# vent_bjt2_i2c_pwm.net
KiCad netlist of a schematic drawn in EAGLE
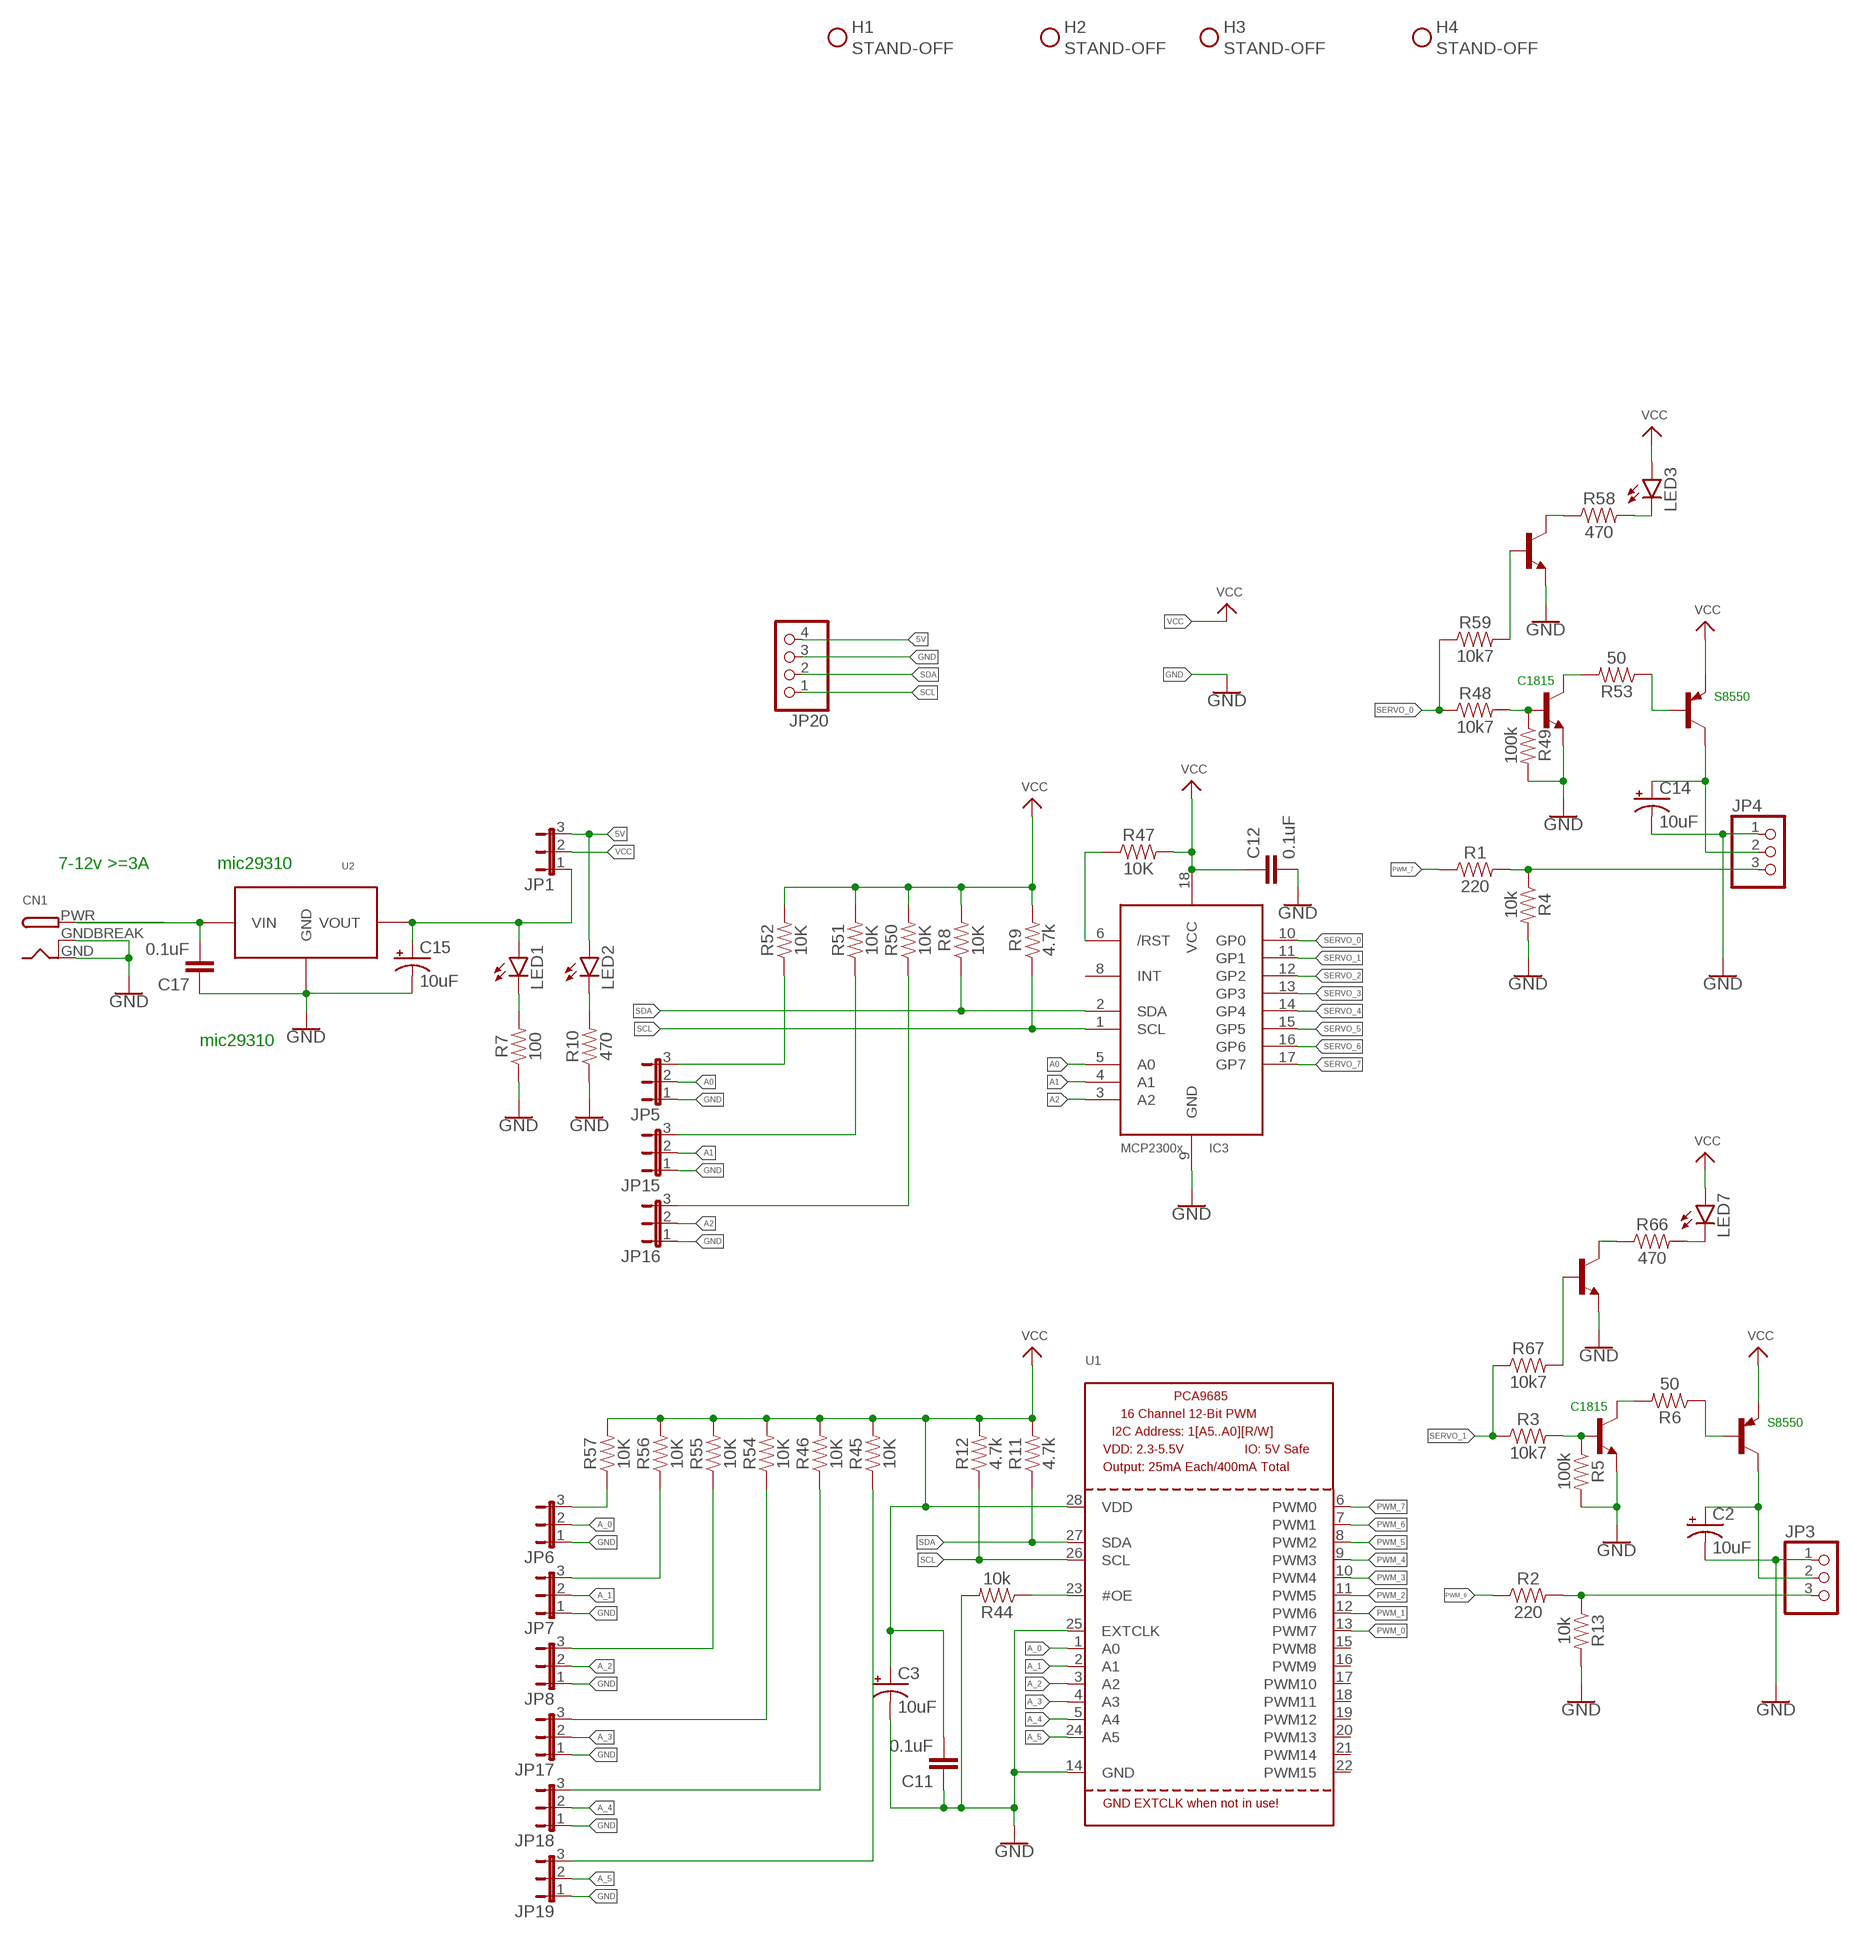
[diagram p0: schematic, sheet 1, part 1 of 2]
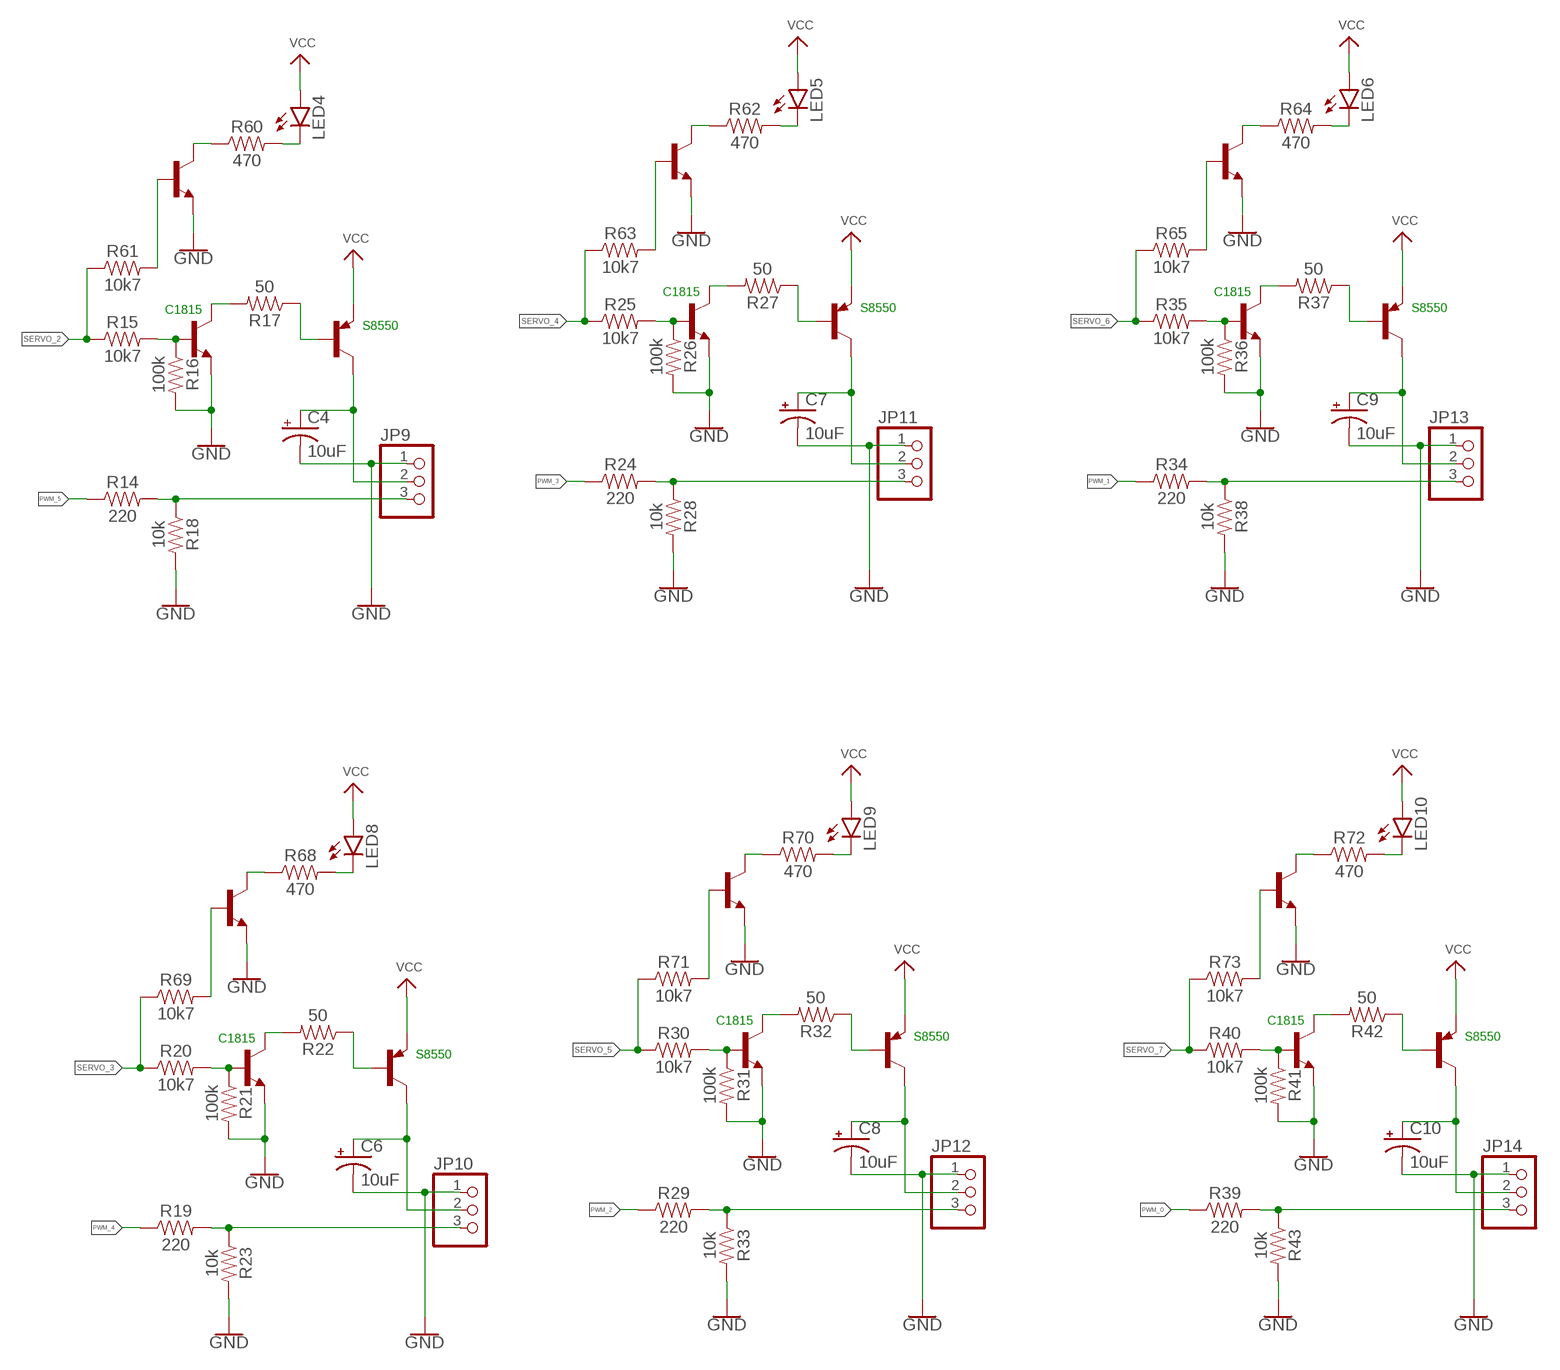
[diagram p1: schematic, sheet 1, part 2 of 2]

(export (version "E")
  (design (tool "Eeschema 10.0.6"))
  (components
    (comp (ref "C2")
      (value "10uF")
      (footprint "eagle-import:CPOL-RADIAL-2.5MM-5MM")
      (libsource (lib "eagle-import") (part "10UF-POLAR-RADIAL-2.5MM-25V-20%"))
    )
    (comp (ref "C3")
      (value "10uF")
      (footprint "eagle-import:CPOL-RADIAL-2.5MM-5MM")
      (libsource (lib "eagle-import") (part "10UF-POLAR-RADIAL-2.5MM-25V-20%"))
    )
    (comp (ref "C4")
      (value "10uF")
      (footprint "eagle-import:CPOL-RADIAL-2.5MM-5MM")
      (libsource (lib "eagle-import") (part "10UF-POLAR-RADIAL-2.5MM-25V-20%"))
    )
    (comp (ref "C6")
      (value "10uF")
      (footprint "eagle-import:CPOL-RADIAL-2.5MM-5MM")
      (libsource (lib "eagle-import") (part "10UF-POLAR-RADIAL-2.5MM-25V-20%"))
    )
    (comp (ref "C7")
      (value "10uF")
      (footprint "eagle-import:CPOL-RADIAL-2.5MM-5MM")
      (libsource (lib "eagle-import") (part "10UF-POLAR-RADIAL-2.5MM-25V-20%"))
    )
    (comp (ref "C8")
      (value "10uF")
      (footprint "eagle-import:CPOL-RADIAL-2.5MM-5MM")
      (libsource (lib "eagle-import") (part "10UF-POLAR-RADIAL-2.5MM-25V-20%"))
    )
    (comp (ref "C9")
      (value "10uF")
      (footprint "eagle-import:CPOL-RADIAL-2.5MM-5MM")
      (libsource (lib "eagle-import") (part "10UF-POLAR-RADIAL-2.5MM-25V-20%"))
    )
    (comp (ref "C10")
      (value "10uF")
      (footprint "eagle-import:CPOL-RADIAL-2.5MM-5MM")
      (libsource (lib "eagle-import") (part "10UF-POLAR-RADIAL-2.5MM-25V-20%"))
    )
    (comp (ref "C11")
      (value "0.1uF")
      (footprint "eagle-import:CAP-PTH-SMALL-KIT")
      (libsource (lib "eagle-import") (part "0.1UF-KIT-EZ-50V-20%"))
    )
    (comp (ref "C12")
      (value "0.1uF")
      (footprint "eagle-import:CAP-PTH-SMALL-KIT")
      (libsource (lib "eagle-import") (part "0.1UF-KIT-EZ-50V-20%"))
    )
    (comp (ref "C14")
      (value "10uF")
      (footprint "eagle-import:CPOL-RADIAL-2.5MM-5MM")
      (libsource (lib "eagle-import") (part "10UF-POLAR-RADIAL-2.5MM-25V-20%"))
    )
    (comp (ref "C15")
      (value "10uF")
      (footprint "eagle-import:CPOL-RADIAL-2.5MM-5MM")
      (libsource (lib "eagle-import") (part "10UF-POLAR-RADIAL-2.5MM-25V-20%"))
    )
    (comp (ref "C17")
      (value "0.1uF")
      (footprint "eagle-import:CAP-PTH-SMALL-KIT")
      (libsource (lib "eagle-import") (part "0.1UF-KIT-EZ-50V-20%"))
    )
    (comp (ref "CN1")
      (value "DCBARRELPTH")
      (footprint "eagle-import:DCJACK_2MM_PTH")
      (libsource (lib "eagle-import") (part "DCBARRELPTH"))
    )
    (comp (ref "H1")
      (value "STAND-OFF")
      (footprint "eagle-import:STAND-OFF")
      (libsource (lib "eagle-import") (part "STAND-OFF"))
    )
    (comp (ref "H2")
      (value "STAND-OFF")
      (footprint "eagle-import:STAND-OFF")
      (libsource (lib "eagle-import") (part "STAND-OFF"))
    )
    (comp (ref "H3")
      (value "STAND-OFF")
      (footprint "eagle-import:STAND-OFF")
      (libsource (lib "eagle-import") (part "STAND-OFF"))
    )
    (comp (ref "H4")
      (value "STAND-OFF")
      (footprint "eagle-import:STAND-OFF")
      (libsource (lib "eagle-import") (part "STAND-OFF"))
    )
    (comp (ref "IC3")
      (value "MCP23008/P")
      (footprint "eagle-import:DIL18")
      (libsource (lib "eagle-import") (part "MCP23008/P"))
    )
    (comp (ref "JP1")
      (value "JP2E")
      (footprint "eagle-import:JP2")
      (libsource (lib "eagle-import") (part "JP2E"))
    )
    (comp (ref "JP3")
      (value "PINHD-1X3")
      (footprint "eagle-import:1X03")
      (libsource (lib "eagle-import") (part "PINHD-1X3"))
    )
    (comp (ref "JP4")
      (value "PINHD-1X3")
      (footprint "eagle-import:1X03")
      (libsource (lib "eagle-import") (part "PINHD-1X3"))
    )
    (comp (ref "JP5")
      (value "JP2E")
      (footprint "eagle-import:JP2")
      (libsource (lib "eagle-import") (part "JP2E"))
    )
    (comp (ref "JP6")
      (value "JP2E")
      (footprint "eagle-import:JP2")
      (libsource (lib "eagle-import") (part "JP2E"))
    )
    (comp (ref "JP7")
      (value "JP2E")
      (footprint "eagle-import:JP2")
      (libsource (lib "eagle-import") (part "JP2E"))
    )
    (comp (ref "JP8")
      (value "JP2E")
      (footprint "eagle-import:JP2")
      (libsource (lib "eagle-import") (part "JP2E"))
    )
    (comp (ref "JP9")
      (value "PINHD-1X3")
      (footprint "eagle-import:1X03")
      (libsource (lib "eagle-import") (part "PINHD-1X3"))
    )
    (comp (ref "JP10")
      (value "PINHD-1X3")
      (footprint "eagle-import:1X03")
      (libsource (lib "eagle-import") (part "PINHD-1X3"))
    )
    (comp (ref "JP11")
      (value "PINHD-1X3")
      (footprint "eagle-import:1X03")
      (libsource (lib "eagle-import") (part "PINHD-1X3"))
    )
    (comp (ref "JP12")
      (value "PINHD-1X3")
      (footprint "eagle-import:1X03")
      (libsource (lib "eagle-import") (part "PINHD-1X3"))
    )
    (comp (ref "JP13")
      (value "PINHD-1X3")
      (footprint "eagle-import:1X03")
      (libsource (lib "eagle-import") (part "PINHD-1X3"))
    )
    (comp (ref "JP14")
      (value "PINHD-1X3")
      (footprint "eagle-import:1X03")
      (libsource (lib "eagle-import") (part "PINHD-1X3"))
    )
    (comp (ref "JP15")
      (value "JP2E")
      (footprint "eagle-import:JP2")
      (libsource (lib "eagle-import") (part "JP2E"))
    )
    (comp (ref "JP16")
      (value "JP2E")
      (footprint "eagle-import:JP2")
      (libsource (lib "eagle-import") (part "JP2E"))
    )
    (comp (ref "JP17")
      (value "JP2E")
      (footprint "eagle-import:JP2")
      (libsource (lib "eagle-import") (part "JP2E"))
    )
    (comp (ref "JP18")
      (value "JP2E")
      (footprint "eagle-import:JP2")
      (libsource (lib "eagle-import") (part "JP2E"))
    )
    (comp (ref "JP19")
      (value "JP2E")
      (footprint "eagle-import:JP2")
      (libsource (lib "eagle-import") (part "JP2E"))
    )
    (comp (ref "JP20")
      (value "PINHD-1X4")
      (footprint "eagle-import:1X04")
      (libsource (lib "eagle-import") (part "PINHD-1X4"))
    )
    (comp (ref "LED1")
      (value "LEDCHIPLED_1206")
      (footprint "eagle-import:CHIPLED_1206")
      (libsource (lib "eagle-import") (part "LEDCHIPLED_1206"))
    )
    (comp (ref "LED2")
      (value "LEDCHIPLED_1206")
      (footprint "eagle-import:CHIPLED_1206")
      (libsource (lib "eagle-import") (part "LEDCHIPLED_1206"))
    )
    (comp (ref "LED3")
      (value "LEDCHIPLED_1206")
      (footprint "eagle-import:CHIPLED_1206")
      (libsource (lib "eagle-import") (part "LEDCHIPLED_1206"))
    )
    (comp (ref "LED4")
      (value "LEDCHIPLED_1206")
      (footprint "eagle-import:CHIPLED_1206")
      (libsource (lib "eagle-import") (part "LEDCHIPLED_1206"))
    )
    (comp (ref "LED5")
      (value "LEDCHIPLED_1206")
      (footprint "eagle-import:CHIPLED_1206")
      (libsource (lib "eagle-import") (part "LEDCHIPLED_1206"))
    )
    (comp (ref "LED6")
      (value "LEDCHIPLED_1206")
      (footprint "eagle-import:CHIPLED_1206")
      (libsource (lib "eagle-import") (part "LEDCHIPLED_1206"))
    )
    (comp (ref "LED7")
      (value "LEDCHIPLED_1206")
      (footprint "eagle-import:CHIPLED_1206")
      (libsource (lib "eagle-import") (part "LEDCHIPLED_1206"))
    )
    (comp (ref "LED8")
      (value "LEDCHIPLED_1206")
      (footprint "eagle-import:CHIPLED_1206")
      (libsource (lib "eagle-import") (part "LEDCHIPLED_1206"))
    )
    (comp (ref "LED9")
      (value "LEDCHIPLED_1206")
      (footprint "eagle-import:CHIPLED_1206")
      (libsource (lib "eagle-import") (part "LEDCHIPLED_1206"))
    )
    (comp (ref "LED10")
      (value "LEDCHIPLED_1206")
      (footprint "eagle-import:CHIPLED_1206")
      (libsource (lib "eagle-import") (part "LEDCHIPLED_1206"))
    )
    (comp (ref "Q1")
      (value "2N2907")
      (footprint "eagle-import:TO92-EBC-OVAL")
      (libsource (lib "eagle-import") (part "2N2907"))
    )
    (comp (ref "Q2")
      (value "2N2907")
      (footprint "eagle-import:TO92-EBC-OVAL")
      (libsource (lib "eagle-import") (part "2N2907"))
    )
    (comp (ref "Q3")
      (value "2N2907")
      (footprint "eagle-import:TO92-EBC-OVAL")
      (libsource (lib "eagle-import") (part "2N2907"))
    )
    (comp (ref "Q4")
      (value "2N2907")
      (footprint "eagle-import:TO92-EBC-OVAL")
      (libsource (lib "eagle-import") (part "2N2907"))
    )
    (comp (ref "Q5")
      (value "2N2907")
      (footprint "eagle-import:TO92-EBC-OVAL")
      (libsource (lib "eagle-import") (part "2N2907"))
    )
    (comp (ref "Q6")
      (value "2N2907")
      (footprint "eagle-import:TO92-EBC-OVAL")
      (libsource (lib "eagle-import") (part "2N2907"))
    )
    (comp (ref "Q7")
      (value "2N2907")
      (footprint "eagle-import:TO92-EBC-OVAL")
      (libsource (lib "eagle-import") (part "2N2907"))
    )
    (comp (ref "Q9")
      (value "2N2907")
      (footprint "eagle-import:TO92-EBC-OVAL")
      (libsource (lib "eagle-import") (part "2N2907"))
    )
    (comp (ref "R1")
      (value "220")
      (footprint "eagle-import:AXIAL-0.3")
      (libsource (lib "eagle-import") (part "10KOHM-HORIZ-1/4W-1%"))
    )
    (comp (ref "R2")
      (value "220")
      (footprint "eagle-import:AXIAL-0.3")
      (libsource (lib "eagle-import") (part "10KOHM-HORIZ-1/4W-1%"))
    )
    (comp (ref "R3")
      (value "10k7")
      (footprint "eagle-import:AXIAL-0.3")
      (libsource (lib "eagle-import") (part "10KOHM-HORIZ-1/4W-1%"))
    )
    (comp (ref "R4")
      (value "10k")
      (footprint "eagle-import:AXIAL-0.3")
      (libsource (lib "eagle-import") (part "10KOHM-HORIZ-1/4W-1%"))
    )
    (comp (ref "R5")
      (value "100k")
      (footprint "eagle-import:AXIAL-0.3")
      (libsource (lib "eagle-import") (part "10KOHM-HORIZ-1/4W-1%"))
    )
    (comp (ref "R6")
      (value "50")
      (footprint "eagle-import:AXIAL-0.3")
      (libsource (lib "eagle-import") (part "10KOHM-HORIZ-1/4W-1%"))
    )
    (comp (ref "R7")
      (value "100")
      (footprint "eagle-import:AXIAL-0.3")
      (libsource (lib "eagle-import") (part "10KOHM-HORIZ-1/4W-1%"))
    )
    (comp (ref "R8")
      (value "10K")
      (footprint "eagle-import:AXIAL-0.3")
      (libsource (lib "eagle-import") (part "10KOHM-HORIZ-1/4W-1%"))
    )
    (comp (ref "R9")
      (value "4.7k")
      (footprint "eagle-import:AXIAL-0.3")
      (libsource (lib "eagle-import") (part "10KOHM-HORIZ-1/4W-1%"))
    )
    (comp (ref "R10")
      (value "470")
      (footprint "eagle-import:AXIAL-0.3")
      (libsource (lib "eagle-import") (part "10KOHM-HORIZ-1/4W-1%"))
    )
    (comp (ref "R11")
      (value "4.7k")
      (footprint "eagle-import:AXIAL-0.3")
      (libsource (lib "eagle-import") (part "10KOHM-HORIZ-1/4W-1%"))
    )
    (comp (ref "R12")
      (value "4.7k")
      (footprint "eagle-import:AXIAL-0.3")
      (libsource (lib "eagle-import") (part "10KOHM-HORIZ-1/4W-1%"))
    )
    (comp (ref "R13")
      (value "10k")
      (footprint "eagle-import:AXIAL-0.3")
      (libsource (lib "eagle-import") (part "10KOHM-HORIZ-1/4W-1%"))
    )
    (comp (ref "R14")
      (value "220")
      (footprint "eagle-import:AXIAL-0.3")
      (libsource (lib "eagle-import") (part "10KOHM-HORIZ-1/4W-1%"))
    )
    (comp (ref "R15")
      (value "10k7")
      (footprint "eagle-import:AXIAL-0.3")
      (libsource (lib "eagle-import") (part "10KOHM-HORIZ-1/4W-1%"))
    )
    (comp (ref "R16")
      (value "100k")
      (footprint "eagle-import:AXIAL-0.3")
      (libsource (lib "eagle-import") (part "10KOHM-HORIZ-1/4W-1%"))
    )
    (comp (ref "R17")
      (value "50")
      (footprint "eagle-import:AXIAL-0.3")
      (libsource (lib "eagle-import") (part "10KOHM-HORIZ-1/4W-1%"))
    )
    (comp (ref "R18")
      (value "10k")
      (footprint "eagle-import:AXIAL-0.3")
      (libsource (lib "eagle-import") (part "10KOHM-HORIZ-1/4W-1%"))
    )
    (comp (ref "R19")
      (value "220")
      (footprint "eagle-import:AXIAL-0.3")
      (libsource (lib "eagle-import") (part "10KOHM-HORIZ-1/4W-1%"))
    )
    (comp (ref "R20")
      (value "10k7")
      (footprint "eagle-import:AXIAL-0.3")
      (libsource (lib "eagle-import") (part "10KOHM-HORIZ-1/4W-1%"))
    )
    (comp (ref "R21")
      (value "100k")
      (footprint "eagle-import:AXIAL-0.3")
      (libsource (lib "eagle-import") (part "10KOHM-HORIZ-1/4W-1%"))
    )
    (comp (ref "R22")
      (value "50")
      (footprint "eagle-import:AXIAL-0.3")
      (libsource (lib "eagle-import") (part "10KOHM-HORIZ-1/4W-1%"))
    )
    (comp (ref "R23")
      (value "10k")
      (footprint "eagle-import:AXIAL-0.3")
      (libsource (lib "eagle-import") (part "10KOHM-HORIZ-1/4W-1%"))
    )
    (comp (ref "R24")
      (value "220")
      (footprint "eagle-import:AXIAL-0.3")
      (libsource (lib "eagle-import") (part "10KOHM-HORIZ-1/4W-1%"))
    )
    (comp (ref "R25")
      (value "10k7")
      (footprint "eagle-import:AXIAL-0.3")
      (libsource (lib "eagle-import") (part "10KOHM-HORIZ-1/4W-1%"))
    )
    (comp (ref "R26")
      (value "100k")
      (footprint "eagle-import:AXIAL-0.3")
      (libsource (lib "eagle-import") (part "10KOHM-HORIZ-1/4W-1%"))
    )
    (comp (ref "R27")
      (value "50")
      (footprint "eagle-import:AXIAL-0.3")
      (libsource (lib "eagle-import") (part "10KOHM-HORIZ-1/4W-1%"))
    )
    (comp (ref "R28")
      (value "10k")
      (footprint "eagle-import:AXIAL-0.3")
      (libsource (lib "eagle-import") (part "10KOHM-HORIZ-1/4W-1%"))
    )
    (comp (ref "R29")
      (value "220")
      (footprint "eagle-import:AXIAL-0.3")
      (libsource (lib "eagle-import") (part "10KOHM-HORIZ-1/4W-1%"))
    )
    (comp (ref "R30")
      (value "10k7")
      (footprint "eagle-import:AXIAL-0.3")
      (libsource (lib "eagle-import") (part "10KOHM-HORIZ-1/4W-1%"))
    )
    (comp (ref "R31")
      (value "100k")
      (footprint "eagle-import:AXIAL-0.3")
      (libsource (lib "eagle-import") (part "10KOHM-HORIZ-1/4W-1%"))
    )
    (comp (ref "R32")
      (value "50")
      (footprint "eagle-import:AXIAL-0.3")
      (libsource (lib "eagle-import") (part "10KOHM-HORIZ-1/4W-1%"))
    )
    (comp (ref "R33")
      (value "10k")
      (footprint "eagle-import:AXIAL-0.3")
      (libsource (lib "eagle-import") (part "10KOHM-HORIZ-1/4W-1%"))
    )
    (comp (ref "R34")
      (value "220")
      (footprint "eagle-import:AXIAL-0.3")
      (libsource (lib "eagle-import") (part "10KOHM-HORIZ-1/4W-1%"))
    )
    (comp (ref "R35")
      (value "10k7")
      (footprint "eagle-import:AXIAL-0.3")
      (libsource (lib "eagle-import") (part "10KOHM-HORIZ-1/4W-1%"))
    )
    (comp (ref "R36")
      (value "100k")
      (footprint "eagle-import:AXIAL-0.3")
      (libsource (lib "eagle-import") (part "10KOHM-HORIZ-1/4W-1%"))
    )
    (comp (ref "R37")
      (value "50")
      (footprint "eagle-import:AXIAL-0.3")
      (libsource (lib "eagle-import") (part "10KOHM-HORIZ-1/4W-1%"))
    )
    (comp (ref "R38")
      (value "10k")
      (footprint "eagle-import:AXIAL-0.3")
      (libsource (lib "eagle-import") (part "10KOHM-HORIZ-1/4W-1%"))
    )
    (comp (ref "R39")
      (value "220")
      (footprint "eagle-import:AXIAL-0.3")
      (libsource (lib "eagle-import") (part "10KOHM-HORIZ-1/4W-1%"))
    )
    (comp (ref "R40")
      (value "10k7")
      (footprint "eagle-import:AXIAL-0.3")
      (libsource (lib "eagle-import") (part "10KOHM-HORIZ-1/4W-1%"))
    )
    (comp (ref "R41")
      (value "100k")
      (footprint "eagle-import:AXIAL-0.3")
      (libsource (lib "eagle-import") (part "10KOHM-HORIZ-1/4W-1%"))
    )
    (comp (ref "R42")
      (value "50")
      (footprint "eagle-import:AXIAL-0.3")
      (libsource (lib "eagle-import") (part "10KOHM-HORIZ-1/4W-1%"))
    )
    (comp (ref "R43")
      (value "10k")
      (footprint "eagle-import:AXIAL-0.3")
      (libsource (lib "eagle-import") (part "10KOHM-HORIZ-1/4W-1%"))
    )
    (comp (ref "R44")
      (value "10k")
      (footprint "eagle-import:AXIAL-0.3")
      (libsource (lib "eagle-import") (part "10KOHM-HORIZ-1/4W-1%"))
    )
    (comp (ref "R45")
      (value "10K")
      (footprint "eagle-import:AXIAL-0.3")
      (libsource (lib "eagle-import") (part "10KOHM-HORIZ-1/4W-1%"))
    )
    (comp (ref "R46")
      (value "10K")
      (footprint "eagle-import:AXIAL-0.3")
      (libsource (lib "eagle-import") (part "10KOHM-HORIZ-1/4W-1%"))
    )
    (comp (ref "R47")
      (value "10K")
      (footprint "eagle-import:AXIAL-0.3")
      (libsource (lib "eagle-import") (part "10KOHM-HORIZ-1/4W-1%"))
    )
    (comp (ref "R48")
      (value "10k7")
      (footprint "eagle-import:AXIAL-0.3")
      (libsource (lib "eagle-import") (part "10KOHM-HORIZ-1/4W-1%"))
    )
    (comp (ref "R49")
      (value "100k")
      (footprint "eagle-import:AXIAL-0.3")
      (libsource (lib "eagle-import") (part "10KOHM-HORIZ-1/4W-1%"))
    )
    (comp (ref "R50")
      (value "10K")
      (footprint "eagle-import:AXIAL-0.3")
      (libsource (lib "eagle-import") (part "10KOHM-HORIZ-1/4W-1%"))
    )
    (comp (ref "R51")
      (value "10K")
      (footprint "eagle-import:AXIAL-0.3")
      (libsource (lib "eagle-import") (part "10KOHM-HORIZ-1/4W-1%"))
    )
    (comp (ref "R52")
      (value "10K")
      (footprint "eagle-import:AXIAL-0.3")
      (libsource (lib "eagle-import") (part "10KOHM-HORIZ-1/4W-1%"))
    )
    (comp (ref "R53")
      (value "50")
      (footprint "eagle-import:AXIAL-0.3")
      (libsource (lib "eagle-import") (part "10KOHM-HORIZ-1/4W-1%"))
    )
    (comp (ref "R54")
      (value "10K")
      (footprint "eagle-import:AXIAL-0.3")
      (libsource (lib "eagle-import") (part "10KOHM-HORIZ-1/4W-1%"))
    )
    (comp (ref "R55")
      (value "10K")
      (footprint "eagle-import:AXIAL-0.3")
      (libsource (lib "eagle-import") (part "10KOHM-HORIZ-1/4W-1%"))
    )
    (comp (ref "R56")
      (value "10K")
      (footprint "eagle-import:AXIAL-0.3")
      (libsource (lib "eagle-import") (part "10KOHM-HORIZ-1/4W-1%"))
    )
    (comp (ref "R57")
      (value "10K")
      (footprint "eagle-import:AXIAL-0.3")
      (libsource (lib "eagle-import") (part "10KOHM-HORIZ-1/4W-1%"))
    )
    (comp (ref "R58")
      (value "470")
      (footprint "eagle-import:AXIAL-0.3")
      (libsource (lib "eagle-import") (part "10KOHM-HORIZ-1/4W-1%"))
    )
    (comp (ref "R59")
      (value "10k7")
      (footprint "eagle-import:AXIAL-0.3")
      (libsource (lib "eagle-import") (part "10KOHM-HORIZ-1/4W-1%"))
    )
    (comp (ref "R60")
      (value "470")
      (footprint "eagle-import:AXIAL-0.3")
      (libsource (lib "eagle-import") (part "10KOHM-HORIZ-1/4W-1%"))
    )
    (comp (ref "R61")
      (value "10k7")
      (footprint "eagle-import:AXIAL-0.3")
      (libsource (lib "eagle-import") (part "10KOHM-HORIZ-1/4W-1%"))
    )
    (comp (ref "R62")
      (value "470")
      (footprint "eagle-import:AXIAL-0.3")
      (libsource (lib "eagle-import") (part "10KOHM-HORIZ-1/4W-1%"))
    )
    (comp (ref "R63")
      (value "10k7")
      (footprint "eagle-import:AXIAL-0.3")
      (libsource (lib "eagle-import") (part "10KOHM-HORIZ-1/4W-1%"))
    )
    (comp (ref "R64")
      (value "470")
      (footprint "eagle-import:AXIAL-0.3")
      (libsource (lib "eagle-import") (part "10KOHM-HORIZ-1/4W-1%"))
    )
    (comp (ref "R65")
      (value "10k7")
      (footprint "eagle-import:AXIAL-0.3")
      (libsource (lib "eagle-import") (part "10KOHM-HORIZ-1/4W-1%"))
    )
    (comp (ref "R66")
      (value "470")
      (footprint "eagle-import:AXIAL-0.3")
      (libsource (lib "eagle-import") (part "10KOHM-HORIZ-1/4W-1%"))
    )
    (comp (ref "R67")
      (value "10k7")
      (footprint "eagle-import:AXIAL-0.3")
      (libsource (lib "eagle-import") (part "10KOHM-HORIZ-1/4W-1%"))
    )
    (comp (ref "R68")
      (value "470")
      (footprint "eagle-import:AXIAL-0.3")
      (libsource (lib "eagle-import") (part "10KOHM-HORIZ-1/4W-1%"))
    )
    (comp (ref "R69")
      (value "10k7")
      (footprint "eagle-import:AXIAL-0.3")
      (libsource (lib "eagle-import") (part "10KOHM-HORIZ-1/4W-1%"))
    )
    (comp (ref "R70")
      (value "470")
      (footprint "eagle-import:AXIAL-0.3")
      (libsource (lib "eagle-import") (part "10KOHM-HORIZ-1/4W-1%"))
    )
    (comp (ref "R71")
      (value "10k7")
      (footprint "eagle-import:AXIAL-0.3")
      (libsource (lib "eagle-import") (part "10KOHM-HORIZ-1/4W-1%"))
    )
    (comp (ref "R72")
      (value "470")
      (footprint "eagle-import:AXIAL-0.3")
      (libsource (lib "eagle-import") (part "10KOHM-HORIZ-1/4W-1%"))
    )
    (comp (ref "R73")
      (value "10k7")
      (footprint "eagle-import:AXIAL-0.3")
      (libsource (lib "eagle-import") (part "10KOHM-HORIZ-1/4W-1%"))
    )
    (comp (ref "T1")
      (value "2SC1815")
      (footprint "eagle-import:TO92-ECB")
      (libsource (lib "eagle-import") (part "2SC1815"))
    )
    (comp (ref "T2")
      (value "2SC1815")
      (footprint "eagle-import:TO92-ECB")
      (libsource (lib "eagle-import") (part "2SC1815"))
    )
    (comp (ref "T3")
      (value "2SC1815")
      (footprint "eagle-import:TO92-ECB")
      (libsource (lib "eagle-import") (part "2SC1815"))
    )
    (comp (ref "T4")
      (value "2SC1815")
      (footprint "eagle-import:TO92-ECB")
      (libsource (lib "eagle-import") (part "2SC1815"))
    )
    (comp (ref "T5")
      (value "2SC1815")
      (footprint "eagle-import:TO92-ECB")
      (libsource (lib "eagle-import") (part "2SC1815"))
    )
    (comp (ref "T6")
      (value "2SC1815")
      (footprint "eagle-import:TO92-ECB")
      (libsource (lib "eagle-import") (part "2SC1815"))
    )
    (comp (ref "T7")
      (value "2SC1815")
      (footprint "eagle-import:TO92-ECB")
      (libsource (lib "eagle-import") (part "2SC1815"))
    )
    (comp (ref "T9")
      (value "2SC1815")
      (footprint "eagle-import:TO92-ECB")
      (libsource (lib "eagle-import") (part "2SC1815"))
    )
    (comp (ref "U1")
      (value "PCA9685")
      (footprint "eagle-import:TSSOP28")
      (libsource (lib "eagle-import") (part "PCA9685"))
    )
    (comp (ref "U2")
      (value "MIC29310_TO-263")
      (footprint "eagle-import:TO263-3")
      (libsource (lib "eagle-import") (part "MIC29310_TO-263"))
    )
    (comp (ref "U3")
      (value "S9018")
      (footprint "eagle-import:TO92-EBC")
      (libsource (lib "eagle-import") (part "S9018"))
    )
    (comp (ref "U4")
      (value "S9018")
      (footprint "eagle-import:TO92-EBC")
      (libsource (lib "eagle-import") (part "S9018"))
    )
    (comp (ref "U5")
      (value "S9018")
      (footprint "eagle-import:TO92-EBC")
      (libsource (lib "eagle-import") (part "S9018"))
    )
    (comp (ref "U6")
      (value "S9018")
      (footprint "eagle-import:TO92-EBC")
      (libsource (lib "eagle-import") (part "S9018"))
    )
    (comp (ref "U7")
      (value "S9018")
      (footprint "eagle-import:TO92-EBC")
      (libsource (lib "eagle-import") (part "S9018"))
    )
    (comp (ref "U8")
      (value "S9018")
      (footprint "eagle-import:TO92-EBC")
      (libsource (lib "eagle-import") (part "S9018"))
    )
    (comp (ref "U9")
      (value "S9018")
      (footprint "eagle-import:TO92-EBC")
      (libsource (lib "eagle-import") (part "S9018"))
    )
    (comp (ref "U10")
      (value "S9018")
      (footprint "eagle-import:TO92-EBC")
      (libsource (lib "eagle-import") (part "S9018"))
    )
  )
  (nets
    (net (code "1") (name "5V") (class "Default")
      (node (ref "JP1") (pin "3") (pinfunction "3_3") (pintype "passive"))
      (node (ref "JP20") (pin "4") (pinfunction "4_4") (pintype "passive"))
      (node (ref "LED2") (pin "A") (pinfunction "A_A") (pintype "passive"))
    )
    (net (code "2") (name "A0") (class "Default")
      (node (ref "IC3") (pin "5") (pinfunction "A0_5") (pintype "input"))
      (node (ref "JP5") (pin "2") (pinfunction "2_2") (pintype "passive"))
    )
    (net (code "3") (name "A1") (class "Default")
      (node (ref "IC3") (pin "4") (pinfunction "A1_4") (pintype "input"))
      (node (ref "JP15") (pin "2") (pinfunction "2_2") (pintype "passive"))
    )
    (net (code "4") (name "A2") (class "Default")
      (node (ref "IC3") (pin "3") (pinfunction "A2_3") (pintype "input"))
      (node (ref "JP16") (pin "2") (pinfunction "2_2") (pintype "passive"))
    )
    (net (code "5") (name "A_0") (class "Default")
      (node (ref "JP6") (pin "2") (pinfunction "2_2") (pintype "passive"))
      (node (ref "U1") (pin "1") (pinfunction "A0_1") (pintype "bidirectional"))
    )
    (net (code "6") (name "A_1") (class "Default")
      (node (ref "JP7") (pin "2") (pinfunction "2_2") (pintype "passive"))
      (node (ref "U1") (pin "2") (pinfunction "A1_2") (pintype "bidirectional"))
    )
    (net (code "7") (name "A_2") (class "Default")
      (node (ref "JP8") (pin "2") (pinfunction "2_2") (pintype "passive"))
      (node (ref "U1") (pin "3") (pinfunction "A2_3") (pintype "bidirectional"))
    )
    (net (code "8") (name "A_3") (class "Default")
      (node (ref "JP17") (pin "2") (pinfunction "2_2") (pintype "passive"))
      (node (ref "U1") (pin "4") (pinfunction "A3_4") (pintype "bidirectional"))
    )
    (net (code "9") (name "A_4") (class "Default")
      (node (ref "JP18") (pin "2") (pinfunction "2_2") (pintype "passive"))
      (node (ref "U1") (pin "5") (pinfunction "A4_5") (pintype "bidirectional"))
    )
    (net (code "10") (name "A_5") (class "Default")
      (node (ref "JP19") (pin "2") (pinfunction "2_2") (pintype "passive"))
      (node (ref "U1") (pin "24") (pinfunction "A5_24") (pintype "bidirectional"))
    )
    (net (code "11") (name "GND") (class "Default")
      (node (ref "C10") (pin "2") (pinfunction "-_2") (pintype "passive"))
      (node (ref "C11") (pin "1") (pinfunction "1_1") (pintype "passive"))
      (node (ref "C12") (pin "2") (pinfunction "2_2") (pintype "passive"))
      (node (ref "C14") (pin "2") (pinfunction "-_2") (pintype "passive"))
      (node (ref "C15") (pin "2") (pinfunction "-_2") (pintype "passive"))
      (node (ref "C17") (pin "1") (pinfunction "1_1") (pintype "passive"))
      (node (ref "C2") (pin "2") (pinfunction "-_2") (pintype "passive"))
      (node (ref "C3") (pin "2") (pinfunction "-_2") (pintype "passive"))
      (node (ref "C4") (pin "2") (pinfunction "-_2") (pintype "passive"))
      (node (ref "C6") (pin "2") (pinfunction "-_2") (pintype "passive"))
      (node (ref "C7") (pin "2") (pinfunction "-_2") (pintype "passive"))
      (node (ref "C8") (pin "2") (pinfunction "-_2") (pintype "passive"))
      (node (ref "C9") (pin "2") (pinfunction "-_2") (pintype "passive"))
      (node (ref "CN1") (pin "GND") (pinfunction "GND_GND") (pintype "power_in"))
      (node (ref "CN1") (pin "GNDBREAK") (pinfunction "GNDBREAK_GNDBREAK") (pintype "power_in"))
      (node (ref "IC3") (pin "9") (pinfunction "GND_9") (pintype "power_in"))
      (node (ref "JP10") (pin "1") (pinfunction "1_1") (pintype "passive"))
      (node (ref "JP11") (pin "1") (pinfunction "1_1") (pintype "passive"))
      (node (ref "JP12") (pin "1") (pinfunction "1_1") (pintype "passive"))
      (node (ref "JP13") (pin "1") (pinfunction "1_1") (pintype "passive"))
      (node (ref "JP14") (pin "1") (pinfunction "1_1") (pintype "passive"))
      (node (ref "JP15") (pin "1") (pinfunction "1_1") (pintype "passive"))
      (node (ref "JP16") (pin "1") (pinfunction "1_1") (pintype "passive"))
      (node (ref "JP17") (pin "1") (pinfunction "1_1") (pintype "passive"))
      (node (ref "JP18") (pin "1") (pinfunction "1_1") (pintype "passive"))
      (node (ref "JP19") (pin "1") (pinfunction "1_1") (pintype "passive"))
      (node (ref "JP20") (pin "3") (pinfunction "3_3") (pintype "passive"))
      (node (ref "JP3") (pin "1") (pinfunction "1_1") (pintype "passive"))
      (node (ref "JP4") (pin "1") (pinfunction "1_1") (pintype "passive"))
      (node (ref "JP5") (pin "1") (pinfunction "1_1") (pintype "passive"))
      (node (ref "JP6") (pin "1") (pinfunction "1_1") (pintype "passive"))
      (node (ref "JP7") (pin "1") (pinfunction "1_1") (pintype "passive"))
      (node (ref "JP8") (pin "1") (pinfunction "1_1") (pintype "passive"))
      (node (ref "JP9") (pin "1") (pinfunction "1_1") (pintype "passive"))
      (node (ref "R10") (pin "P$1") (pinfunction "1_P$1") (pintype "passive"))
      (node (ref "R13") (pin "P$2") (pinfunction "2_P$2") (pintype "passive"))
      (node (ref "R16") (pin "P$2") (pinfunction "2_P$2") (pintype "passive"))
      (node (ref "R18") (pin "P$2") (pinfunction "2_P$2") (pintype "passive"))
      (node (ref "R21") (pin "P$2") (pinfunction "2_P$2") (pintype "passive"))
      (node (ref "R23") (pin "P$2") (pinfunction "2_P$2") (pintype "passive"))
      (node (ref "R26") (pin "P$2") (pinfunction "2_P$2") (pintype "passive"))
      (node (ref "R28") (pin "P$2") (pinfunction "2_P$2") (pintype "passive"))
      (node (ref "R31") (pin "P$2") (pinfunction "2_P$2") (pintype "passive"))
      (node (ref "R33") (pin "P$2") (pinfunction "2_P$2") (pintype "passive"))
      (node (ref "R36") (pin "P$2") (pinfunction "2_P$2") (pintype "passive"))
      (node (ref "R38") (pin "P$2") (pinfunction "2_P$2") (pintype "passive"))
      (node (ref "R4") (pin "P$2") (pinfunction "2_P$2") (pintype "passive"))
      (node (ref "R41") (pin "P$2") (pinfunction "2_P$2") (pintype "passive"))
      (node (ref "R43") (pin "P$2") (pinfunction "2_P$2") (pintype "passive"))
      (node (ref "R44") (pin "P$2") (pinfunction "2_P$2") (pintype "passive"))
      (node (ref "R49") (pin "P$2") (pinfunction "2_P$2") (pintype "passive"))
      (node (ref "R5") (pin "P$2") (pinfunction "2_P$2") (pintype "passive"))
      (node (ref "R7") (pin "P$1") (pinfunction "1_P$1") (pintype "passive"))
      (node (ref "T1") (pin "E") (pinfunction "E_E") (pintype "passive"))
      (node (ref "T2") (pin "E") (pinfunction "E_E") (pintype "passive"))
      (node (ref "T3") (pin "E") (pinfunction "E_E") (pintype "passive"))
      (node (ref "T4") (pin "E") (pinfunction "E_E") (pintype "passive"))
      (node (ref "T5") (pin "E") (pinfunction "E_E") (pintype "passive"))
      (node (ref "T6") (pin "E") (pinfunction "E_E") (pintype "passive"))
      (node (ref "T7") (pin "E") (pinfunction "E_E") (pintype "passive"))
      (node (ref "T9") (pin "E") (pinfunction "E_E") (pintype "passive"))
      (node (ref "U1") (pin "14") (pinfunction "GND_14") (pintype "power_in"))
      (node (ref "U1") (pin "25") (pinfunction "EXTCLK_25") (pintype "input"))
      (node (ref "U10") (pin "E") (pinfunction "E_E") (pintype "passive"))
      (node (ref "U2") (pin "2") (pinfunction "GND_2") (pintype "power_in"))
      (node (ref "U2") (pin "TAB") (pinfunction "GND_TAB") (pintype "power_in"))
      (node (ref "U3") (pin "E") (pinfunction "E_E") (pintype "passive"))
      (node (ref "U4") (pin "E") (pinfunction "E_E") (pintype "passive"))
      (node (ref "U5") (pin "E") (pinfunction "E_E") (pintype "passive"))
      (node (ref "U6") (pin "E") (pinfunction "E_E") (pintype "passive"))
      (node (ref "U7") (pin "E") (pinfunction "E_E") (pintype "passive"))
      (node (ref "U8") (pin "E") (pinfunction "E_E") (pintype "passive"))
      (node (ref "U9") (pin "E") (pinfunction "E_E") (pintype "passive"))
    )
    (net (code "12") (name "Net-(C2-+)") (class "Default")
      (node (ref "C2") (pin "1") (pinfunction "+_1") (pintype "passive"))
      (node (ref "JP3") (pin "2") (pinfunction "2_2") (pintype "passive"))
      (node (ref "Q1") (pin "C") (pinfunction "C_C") (pintype "passive"))
    )
    (net (code "13") (name "Net-(C4-+)") (class "Default")
      (node (ref "C4") (pin "1") (pinfunction "+_1") (pintype "passive"))
      (node (ref "JP9") (pin "2") (pinfunction "2_2") (pintype "passive"))
      (node (ref "Q2") (pin "C") (pinfunction "C_C") (pintype "passive"))
    )
    (net (code "14") (name "Net-(C6-+)") (class "Default")
      (node (ref "C6") (pin "1") (pinfunction "+_1") (pintype "passive"))
      (node (ref "JP10") (pin "2") (pinfunction "2_2") (pintype "passive"))
      (node (ref "Q3") (pin "C") (pinfunction "C_C") (pintype "passive"))
    )
    (net (code "15") (name "Net-(C7-+)") (class "Default")
      (node (ref "C7") (pin "1") (pinfunction "+_1") (pintype "passive"))
      (node (ref "JP11") (pin "2") (pinfunction "2_2") (pintype "passive"))
      (node (ref "Q4") (pin "C") (pinfunction "C_C") (pintype "passive"))
    )
    (net (code "16") (name "Net-(C8-+)") (class "Default")
      (node (ref "C8") (pin "1") (pinfunction "+_1") (pintype "passive"))
      (node (ref "JP12") (pin "2") (pinfunction "2_2") (pintype "passive"))
      (node (ref "Q5") (pin "C") (pinfunction "C_C") (pintype "passive"))
    )
    (net (code "17") (name "Net-(C9-+)") (class "Default")
      (node (ref "C9") (pin "1") (pinfunction "+_1") (pintype "passive"))
      (node (ref "JP13") (pin "2") (pinfunction "2_2") (pintype "passive"))
      (node (ref "Q6") (pin "C") (pinfunction "C_C") (pintype "passive"))
    )
    (net (code "18") (name "Net-(C10-+)") (class "Default")
      (node (ref "C10") (pin "1") (pinfunction "+_1") (pintype "passive"))
      (node (ref "JP14") (pin "2") (pinfunction "2_2") (pintype "passive"))
      (node (ref "Q7") (pin "C") (pinfunction "C_C") (pintype "passive"))
    )
    (net (code "19") (name "Net-(C14-+)") (class "Default")
      (node (ref "C14") (pin "1") (pinfunction "+_1") (pintype "passive"))
      (node (ref "JP4") (pin "2") (pinfunction "2_2") (pintype "passive"))
      (node (ref "Q9") (pin "C") (pinfunction "C_C") (pintype "passive"))
    )
    (net (code "20") (name "Net-(C15-+)") (class "Default")
      (node (ref "C15") (pin "1") (pinfunction "+_1") (pintype "passive"))
      (node (ref "JP1") (pin "1") (pinfunction "1_1") (pintype "passive"))
      (node (ref "LED1") (pin "A") (pinfunction "A_A") (pintype "passive"))
      (node (ref "U2") (pin "3") (pinfunction "VOUT_3") (pintype "power_in"))
    )
    (net (code "21") (name "Net-(IC3-{slash}RST)") (class "Default")
      (node (ref "IC3") (pin "6") (pinfunction "/RST_6") (pintype "input"))
      (node (ref "R47") (pin "P$1") (pinfunction "1_P$1") (pintype "passive"))
    )
    (net (code "22") (name "Net-(R1-2)") (class "Default")
      (node (ref "JP4") (pin "3") (pinfunction "3_3") (pintype "passive"))
      (node (ref "R1") (pin "P$2") (pinfunction "2_P$2") (pintype "passive"))
      (node (ref "R4") (pin "P$1") (pinfunction "1_P$1") (pintype "passive"))
    )
    (net (code "23") (name "Net-(R3-2)") (class "Default")
      (node (ref "R3") (pin "P$2") (pinfunction "2_P$2") (pintype "passive"))
      (node (ref "R5") (pin "P$1") (pinfunction "1_P$1") (pintype "passive"))
      (node (ref "T1") (pin "B") (pinfunction "B_B") (pintype "passive"))
    )
    (net (code "24") (name "Net-(R6-1)") (class "Default")
      (node (ref "Q1") (pin "B") (pinfunction "B_B") (pintype "passive"))
      (node (ref "R6") (pin "P$1") (pinfunction "1_P$1") (pintype "passive"))
    )
    (net (code "25") (name "Net-(R6-2)") (class "Default")
      (node (ref "R6") (pin "P$2") (pinfunction "2_P$2") (pintype "passive"))
      (node (ref "T1") (pin "C") (pinfunction "C_C") (pintype "passive"))
    )
    (net (code "26") (name "Net-(R7-2)") (class "Default")
      (node (ref "LED1") (pin "C") (pinfunction "C_C") (pintype "passive"))
      (node (ref "R7") (pin "P$2") (pinfunction "2_P$2") (pintype "passive"))
    )
    (net (code "27") (name "Net-(R10-2)") (class "Default")
      (node (ref "LED2") (pin "C") (pinfunction "C_C") (pintype "passive"))
      (node (ref "R10") (pin "P$2") (pinfunction "2_P$2") (pintype "passive"))
    )
    (net (code "28") (name "Net-(R13-1)") (class "Default")
      (node (ref "JP3") (pin "3") (pinfunction "3_3") (pintype "passive"))
      (node (ref "R13") (pin "P$1") (pinfunction "1_P$1") (pintype "passive"))
      (node (ref "R2") (pin "P$2") (pinfunction "2_P$2") (pintype "passive"))
    )
    (net (code "29") (name "Net-(R14-2)") (class "Default")
      (node (ref "JP9") (pin "3") (pinfunction "3_3") (pintype "passive"))
      (node (ref "R14") (pin "P$2") (pinfunction "2_P$2") (pintype "passive"))
      (node (ref "R18") (pin "P$1") (pinfunction "1_P$1") (pintype "passive"))
    )
    (net (code "30") (name "Net-(R15-2)") (class "Default")
      (node (ref "R15") (pin "P$2") (pinfunction "2_P$2") (pintype "passive"))
      (node (ref "R16") (pin "P$1") (pinfunction "1_P$1") (pintype "passive"))
      (node (ref "T2") (pin "B") (pinfunction "B_B") (pintype "passive"))
    )
    (net (code "31") (name "Net-(R17-1)") (class "Default")
      (node (ref "Q2") (pin "B") (pinfunction "B_B") (pintype "passive"))
      (node (ref "R17") (pin "P$1") (pinfunction "1_P$1") (pintype "passive"))
    )
    (net (code "32") (name "Net-(R17-2)") (class "Default")
      (node (ref "R17") (pin "P$2") (pinfunction "2_P$2") (pintype "passive"))
      (node (ref "T2") (pin "C") (pinfunction "C_C") (pintype "passive"))
    )
    (net (code "33") (name "Net-(R19-2)") (class "Default")
      (node (ref "JP10") (pin "3") (pinfunction "3_3") (pintype "passive"))
      (node (ref "R19") (pin "P$2") (pinfunction "2_P$2") (pintype "passive"))
      (node (ref "R23") (pin "P$1") (pinfunction "1_P$1") (pintype "passive"))
    )
    (net (code "34") (name "Net-(R20-2)") (class "Default")
      (node (ref "R20") (pin "P$2") (pinfunction "2_P$2") (pintype "passive"))
      (node (ref "R21") (pin "P$1") (pinfunction "1_P$1") (pintype "passive"))
      (node (ref "T3") (pin "B") (pinfunction "B_B") (pintype "passive"))
    )
    (net (code "35") (name "Net-(R22-1)") (class "Default")
      (node (ref "Q3") (pin "B") (pinfunction "B_B") (pintype "passive"))
      (node (ref "R22") (pin "P$1") (pinfunction "1_P$1") (pintype "passive"))
    )
    (net (code "36") (name "Net-(R22-2)") (class "Default")
      (node (ref "R22") (pin "P$2") (pinfunction "2_P$2") (pintype "passive"))
      (node (ref "T3") (pin "C") (pinfunction "C_C") (pintype "passive"))
    )
    (net (code "37") (name "Net-(R24-2)") (class "Default")
      (node (ref "JP11") (pin "3") (pinfunction "3_3") (pintype "passive"))
      (node (ref "R24") (pin "P$2") (pinfunction "2_P$2") (pintype "passive"))
      (node (ref "R28") (pin "P$1") (pinfunction "1_P$1") (pintype "passive"))
    )
    (net (code "38") (name "Net-(R25-2)") (class "Default")
      (node (ref "R25") (pin "P$2") (pinfunction "2_P$2") (pintype "passive"))
      (node (ref "R26") (pin "P$1") (pinfunction "1_P$1") (pintype "passive"))
      (node (ref "T4") (pin "B") (pinfunction "B_B") (pintype "passive"))
    )
    (net (code "39") (name "Net-(R27-1)") (class "Default")
      (node (ref "Q4") (pin "B") (pinfunction "B_B") (pintype "passive"))
      (node (ref "R27") (pin "P$1") (pinfunction "1_P$1") (pintype "passive"))
    )
    (net (code "40") (name "Net-(R27-2)") (class "Default")
      (node (ref "R27") (pin "P$2") (pinfunction "2_P$2") (pintype "passive"))
      (node (ref "T4") (pin "C") (pinfunction "C_C") (pintype "passive"))
    )
    (net (code "41") (name "Net-(R29-2)") (class "Default")
      (node (ref "JP12") (pin "3") (pinfunction "3_3") (pintype "passive"))
      (node (ref "R29") (pin "P$2") (pinfunction "2_P$2") (pintype "passive"))
      (node (ref "R33") (pin "P$1") (pinfunction "1_P$1") (pintype "passive"))
    )
    (net (code "42") (name "Net-(R30-2)") (class "Default")
      (node (ref "R30") (pin "P$2") (pinfunction "2_P$2") (pintype "passive"))
      (node (ref "R31") (pin "P$1") (pinfunction "1_P$1") (pintype "passive"))
      (node (ref "T5") (pin "B") (pinfunction "B_B") (pintype "passive"))
    )
    (net (code "43") (name "Net-(R32-1)") (class "Default")
      (node (ref "Q5") (pin "B") (pinfunction "B_B") (pintype "passive"))
      (node (ref "R32") (pin "P$1") (pinfunction "1_P$1") (pintype "passive"))
    )
    (net (code "44") (name "Net-(R32-2)") (class "Default")
      (node (ref "R32") (pin "P$2") (pinfunction "2_P$2") (pintype "passive"))
      (node (ref "T5") (pin "C") (pinfunction "C_C") (pintype "passive"))
    )
    (net (code "45") (name "Net-(R34-2)") (class "Default")
      (node (ref "JP13") (pin "3") (pinfunction "3_3") (pintype "passive"))
      (node (ref "R34") (pin "P$2") (pinfunction "2_P$2") (pintype "passive"))
      (node (ref "R38") (pin "P$1") (pinfunction "1_P$1") (pintype "passive"))
    )
    (net (code "46") (name "Net-(R35-2)") (class "Default")
      (node (ref "R35") (pin "P$2") (pinfunction "2_P$2") (pintype "passive"))
      (node (ref "R36") (pin "P$1") (pinfunction "1_P$1") (pintype "passive"))
      (node (ref "T6") (pin "B") (pinfunction "B_B") (pintype "passive"))
    )
    (net (code "47") (name "Net-(R37-1)") (class "Default")
      (node (ref "Q6") (pin "B") (pinfunction "B_B") (pintype "passive"))
      (node (ref "R37") (pin "P$1") (pinfunction "1_P$1") (pintype "passive"))
    )
    (net (code "48") (name "Net-(R37-2)") (class "Default")
      (node (ref "R37") (pin "P$2") (pinfunction "2_P$2") (pintype "passive"))
      (node (ref "T6") (pin "C") (pinfunction "C_C") (pintype "passive"))
    )
    (net (code "49") (name "Net-(R39-2)") (class "Default")
      (node (ref "JP14") (pin "3") (pinfunction "3_3") (pintype "passive"))
      (node (ref "R39") (pin "P$2") (pinfunction "2_P$2") (pintype "passive"))
      (node (ref "R43") (pin "P$1") (pinfunction "1_P$1") (pintype "passive"))
    )
    (net (code "50") (name "Net-(R40-2)") (class "Default")
      (node (ref "R40") (pin "P$2") (pinfunction "2_P$2") (pintype "passive"))
      (node (ref "R41") (pin "P$1") (pinfunction "1_P$1") (pintype "passive"))
      (node (ref "T7") (pin "B") (pinfunction "B_B") (pintype "passive"))
    )
    (net (code "51") (name "Net-(R42-1)") (class "Default")
      (node (ref "Q7") (pin "B") (pinfunction "B_B") (pintype "passive"))
      (node (ref "R42") (pin "P$1") (pinfunction "1_P$1") (pintype "passive"))
    )
    (net (code "52") (name "Net-(R42-2)") (class "Default")
      (node (ref "R42") (pin "P$2") (pinfunction "2_P$2") (pintype "passive"))
      (node (ref "T7") (pin "C") (pinfunction "C_C") (pintype "passive"))
    )
    (net (code "53") (name "Net-(R44-1)") (class "Default")
      (node (ref "R44") (pin "P$1") (pinfunction "1_P$1") (pintype "passive"))
      (node (ref "U1") (pin "23") (pinfunction "#OE_23") (pintype "input"))
    )
    (net (code "54") (name "Net-(R45-1)") (class "Default")
      (node (ref "JP19") (pin "3") (pinfunction "3_3") (pintype "passive"))
      (node (ref "R45") (pin "P$1") (pinfunction "1_P$1") (pintype "passive"))
    )
    (net (code "55") (name "Net-(R46-1)") (class "Default")
      (node (ref "JP18") (pin "3") (pinfunction "3_3") (pintype "passive"))
      (node (ref "R46") (pin "P$1") (pinfunction "1_P$1") (pintype "passive"))
    )
    (net (code "56") (name "Net-(R48-2)") (class "Default")
      (node (ref "R48") (pin "P$2") (pinfunction "2_P$2") (pintype "passive"))
      (node (ref "R49") (pin "P$1") (pinfunction "1_P$1") (pintype "passive"))
      (node (ref "T9") (pin "B") (pinfunction "B_B") (pintype "passive"))
    )
    (net (code "57") (name "Net-(R50-1)") (class "Default")
      (node (ref "JP16") (pin "3") (pinfunction "3_3") (pintype "passive"))
      (node (ref "R50") (pin "P$1") (pinfunction "1_P$1") (pintype "passive"))
    )
    (net (code "58") (name "Net-(R51-1)") (class "Default")
      (node (ref "JP15") (pin "3") (pinfunction "3_3") (pintype "passive"))
      (node (ref "R51") (pin "P$1") (pinfunction "1_P$1") (pintype "passive"))
    )
    (net (code "59") (name "Net-(R52-1)") (class "Default")
      (node (ref "JP5") (pin "3") (pinfunction "3_3") (pintype "passive"))
      (node (ref "R52") (pin "P$1") (pinfunction "1_P$1") (pintype "passive"))
    )
    (net (code "60") (name "Net-(R53-1)") (class "Default")
      (node (ref "Q9") (pin "B") (pinfunction "B_B") (pintype "passive"))
      (node (ref "R53") (pin "P$1") (pinfunction "1_P$1") (pintype "passive"))
    )
    (net (code "61") (name "Net-(R53-2)") (class "Default")
      (node (ref "R53") (pin "P$2") (pinfunction "2_P$2") (pintype "passive"))
      (node (ref "T9") (pin "C") (pinfunction "C_C") (pintype "passive"))
    )
    (net (code "62") (name "Net-(R54-1)") (class "Default")
      (node (ref "JP17") (pin "3") (pinfunction "3_3") (pintype "passive"))
      (node (ref "R54") (pin "P$1") (pinfunction "1_P$1") (pintype "passive"))
    )
    (net (code "63") (name "Net-(R55-1)") (class "Default")
      (node (ref "JP8") (pin "3") (pinfunction "3_3") (pintype "passive"))
      (node (ref "R55") (pin "P$1") (pinfunction "1_P$1") (pintype "passive"))
    )
    (net (code "64") (name "Net-(R56-1)") (class "Default")
      (node (ref "JP7") (pin "3") (pinfunction "3_3") (pintype "passive"))
      (node (ref "R56") (pin "P$1") (pinfunction "1_P$1") (pintype "passive"))
    )
    (net (code "65") (name "Net-(R57-1)") (class "Default")
      (node (ref "JP6") (pin "3") (pinfunction "3_3") (pintype "passive"))
      (node (ref "R57") (pin "P$1") (pinfunction "1_P$1") (pintype "passive"))
    )
    (net (code "66") (name "Net-(R58-1)") (class "Default")
      (node (ref "R58") (pin "P$1") (pinfunction "1_P$1") (pintype "passive"))
      (node (ref "U3") (pin "C") (pinfunction "C_C") (pintype "passive"))
    )
    (net (code "67") (name "Net-(R58-2)") (class "Default")
      (node (ref "LED3") (pin "C") (pinfunction "C_C") (pintype "passive"))
      (node (ref "R58") (pin "P$2") (pinfunction "2_P$2") (pintype "passive"))
    )
    (net (code "68") (name "Net-(R59-2)") (class "Default")
      (node (ref "R59") (pin "P$2") (pinfunction "2_P$2") (pintype "passive"))
      (node (ref "U3") (pin "B") (pinfunction "B_B") (pintype "passive"))
    )
    (net (code "69") (name "Net-(R60-1)") (class "Default")
      (node (ref "R60") (pin "P$1") (pinfunction "1_P$1") (pintype "passive"))
      (node (ref "U4") (pin "C") (pinfunction "C_C") (pintype "passive"))
    )
    (net (code "70") (name "Net-(R60-2)") (class "Default")
      (node (ref "LED4") (pin "C") (pinfunction "C_C") (pintype "passive"))
      (node (ref "R60") (pin "P$2") (pinfunction "2_P$2") (pintype "passive"))
    )
    (net (code "71") (name "Net-(R61-2)") (class "Default")
      (node (ref "R61") (pin "P$2") (pinfunction "2_P$2") (pintype "passive"))
      (node (ref "U4") (pin "B") (pinfunction "B_B") (pintype "passive"))
    )
    (net (code "72") (name "Net-(R62-1)") (class "Default")
      (node (ref "R62") (pin "P$1") (pinfunction "1_P$1") (pintype "passive"))
      (node (ref "U5") (pin "C") (pinfunction "C_C") (pintype "passive"))
    )
    (net (code "73") (name "Net-(R62-2)") (class "Default")
      (node (ref "LED5") (pin "C") (pinfunction "C_C") (pintype "passive"))
      (node (ref "R62") (pin "P$2") (pinfunction "2_P$2") (pintype "passive"))
    )
    (net (code "74") (name "Net-(R63-2)") (class "Default")
      (node (ref "R63") (pin "P$2") (pinfunction "2_P$2") (pintype "passive"))
      (node (ref "U5") (pin "B") (pinfunction "B_B") (pintype "passive"))
    )
    (net (code "75") (name "Net-(R64-1)") (class "Default")
      (node (ref "R64") (pin "P$1") (pinfunction "1_P$1") (pintype "passive"))
      (node (ref "U6") (pin "C") (pinfunction "C_C") (pintype "passive"))
    )
    (net (code "76") (name "Net-(R64-2)") (class "Default")
      (node (ref "LED6") (pin "C") (pinfunction "C_C") (pintype "passive"))
      (node (ref "R64") (pin "P$2") (pinfunction "2_P$2") (pintype "passive"))
    )
    (net (code "77") (name "Net-(R65-2)") (class "Default")
      (node (ref "R65") (pin "P$2") (pinfunction "2_P$2") (pintype "passive"))
      (node (ref "U6") (pin "B") (pinfunction "B_B") (pintype "passive"))
    )
    (net (code "78") (name "Net-(R66-1)") (class "Default")
      (node (ref "R66") (pin "P$1") (pinfunction "1_P$1") (pintype "passive"))
      (node (ref "U7") (pin "C") (pinfunction "C_C") (pintype "passive"))
    )
    (net (code "79") (name "Net-(R66-2)") (class "Default")
      (node (ref "LED7") (pin "C") (pinfunction "C_C") (pintype "passive"))
      (node (ref "R66") (pin "P$2") (pinfunction "2_P$2") (pintype "passive"))
    )
    (net (code "80") (name "Net-(R67-2)") (class "Default")
      (node (ref "R67") (pin "P$2") (pinfunction "2_P$2") (pintype "passive"))
      (node (ref "U7") (pin "B") (pinfunction "B_B") (pintype "passive"))
    )
    (net (code "81") (name "Net-(R68-1)") (class "Default")
      (node (ref "R68") (pin "P$1") (pinfunction "1_P$1") (pintype "passive"))
      (node (ref "U8") (pin "C") (pinfunction "C_C") (pintype "passive"))
    )
    (net (code "82") (name "Net-(R68-2)") (class "Default")
      (node (ref "LED8") (pin "C") (pinfunction "C_C") (pintype "passive"))
      (node (ref "R68") (pin "P$2") (pinfunction "2_P$2") (pintype "passive"))
    )
    (net (code "83") (name "Net-(R69-2)") (class "Default")
      (node (ref "R69") (pin "P$2") (pinfunction "2_P$2") (pintype "passive"))
      (node (ref "U8") (pin "B") (pinfunction "B_B") (pintype "passive"))
    )
    (net (code "84") (name "Net-(R70-1)") (class "Default")
      (node (ref "R70") (pin "P$1") (pinfunction "1_P$1") (pintype "passive"))
      (node (ref "U9") (pin "C") (pinfunction "C_C") (pintype "passive"))
    )
    (net (code "85") (name "Net-(R70-2)") (class "Default")
      (node (ref "LED9") (pin "C") (pinfunction "C_C") (pintype "passive"))
      (node (ref "R70") (pin "P$2") (pinfunction "2_P$2") (pintype "passive"))
    )
    (net (code "86") (name "Net-(R71-2)") (class "Default")
      (node (ref "R71") (pin "P$2") (pinfunction "2_P$2") (pintype "passive"))
      (node (ref "U9") (pin "B") (pinfunction "B_B") (pintype "passive"))
    )
    (net (code "87") (name "Net-(R72-1)") (class "Default")
      (node (ref "R72") (pin "P$1") (pinfunction "1_P$1") (pintype "passive"))
      (node (ref "U10") (pin "C") (pinfunction "C_C") (pintype "passive"))
    )
    (net (code "88") (name "Net-(R72-2)") (class "Default")
      (node (ref "LED10") (pin "C") (pinfunction "C_C") (pintype "passive"))
      (node (ref "R72") (pin "P$2") (pinfunction "2_P$2") (pintype "passive"))
    )
    (net (code "89") (name "Net-(R73-2)") (class "Default")
      (node (ref "R73") (pin "P$2") (pinfunction "2_P$2") (pintype "passive"))
      (node (ref "U10") (pin "B") (pinfunction "B_B") (pintype "passive"))
    )
    (net (code "90") (name "Net-(U2-VIN)") (class "Default")
      (node (ref "C17") (pin "2") (pinfunction "2_2") (pintype "passive"))
      (node (ref "CN1") (pin "PWR") (pinfunction "PWR_PWR") (pintype "power_in"))
      (node (ref "U2") (pin "1") (pinfunction "VIN_1") (pintype "power_in"))
    )
    (net (code "91") (name "PWM_0") (class "Default")
      (node (ref "R39") (pin "P$1") (pinfunction "1_P$1") (pintype "passive"))
      (node (ref "U1") (pin "13") (pinfunction "PWM7_13") (pintype "output"))
    )
    (net (code "92") (name "PWM_1") (class "Default")
      (node (ref "R34") (pin "P$1") (pinfunction "1_P$1") (pintype "passive"))
      (node (ref "U1") (pin "12") (pinfunction "PWM6_12") (pintype "output"))
    )
    (net (code "93") (name "PWM_2") (class "Default")
      (node (ref "R29") (pin "P$1") (pinfunction "1_P$1") (pintype "passive"))
      (node (ref "U1") (pin "11") (pinfunction "PWM5_11") (pintype "output"))
    )
    (net (code "94") (name "PWM_3") (class "Default")
      (node (ref "R24") (pin "P$1") (pinfunction "1_P$1") (pintype "passive"))
      (node (ref "U1") (pin "10") (pinfunction "PWM4_10") (pintype "output"))
    )
    (net (code "95") (name "PWM_4") (class "Default")
      (node (ref "R19") (pin "P$1") (pinfunction "1_P$1") (pintype "passive"))
      (node (ref "U1") (pin "9") (pinfunction "PWM3_9") (pintype "output"))
    )
    (net (code "96") (name "PWM_5") (class "Default")
      (node (ref "R14") (pin "P$1") (pinfunction "1_P$1") (pintype "passive"))
      (node (ref "U1") (pin "8") (pinfunction "PWM2_8") (pintype "output"))
    )
    (net (code "97") (name "PWM_6") (class "Default")
      (node (ref "R2") (pin "P$1") (pinfunction "1_P$1") (pintype "passive"))
      (node (ref "U1") (pin "7") (pinfunction "PWM1_7") (pintype "output"))
    )
    (net (code "98") (name "PWM_7") (class "Default")
      (node (ref "R1") (pin "P$1") (pinfunction "1_P$1") (pintype "passive"))
      (node (ref "U1") (pin "6") (pinfunction "PWM0_6") (pintype "output"))
    )
    (net (code "99") (name "SCL") (class "Default")
      (node (ref "IC3") (pin "1") (pinfunction "SCL_1") (pintype "bidirectional"))
      (node (ref "JP20") (pin "1") (pinfunction "1_1") (pintype "passive"))
      (node (ref "R12") (pin "P$1") (pinfunction "1_P$1") (pintype "passive"))
      (node (ref "R9") (pin "P$1") (pinfunction "1_P$1") (pintype "passive"))
      (node (ref "U1") (pin "26") (pinfunction "SCL_26") (pintype "bidirectional"))
    )
    (net (code "100") (name "SDA") (class "Default")
      (node (ref "IC3") (pin "2") (pinfunction "SDA_2") (pintype "bidirectional"))
      (node (ref "JP20") (pin "2") (pinfunction "2_2") (pintype "passive"))
      (node (ref "R11") (pin "P$1") (pinfunction "1_P$1") (pintype "passive"))
      (node (ref "R8") (pin "P$1") (pinfunction "1_P$1") (pintype "passive"))
      (node (ref "U1") (pin "27") (pinfunction "SDA_27") (pintype "bidirectional"))
    )
    (net (code "101") (name "SERVO_0") (class "Default")
      (node (ref "IC3") (pin "10") (pinfunction "GP0_10") (pintype "bidirectional"))
      (node (ref "R48") (pin "P$1") (pinfunction "1_P$1") (pintype "passive"))
      (node (ref "R59") (pin "P$1") (pinfunction "1_P$1") (pintype "passive"))
    )
    (net (code "102") (name "SERVO_1") (class "Default")
      (node (ref "IC3") (pin "11") (pinfunction "GP1_11") (pintype "bidirectional"))
      (node (ref "R3") (pin "P$1") (pinfunction "1_P$1") (pintype "passive"))
      (node (ref "R67") (pin "P$1") (pinfunction "1_P$1") (pintype "passive"))
    )
    (net (code "103") (name "SERVO_2") (class "Default")
      (node (ref "IC3") (pin "12") (pinfunction "GP2_12") (pintype "bidirectional"))
      (node (ref "R15") (pin "P$1") (pinfunction "1_P$1") (pintype "passive"))
      (node (ref "R61") (pin "P$1") (pinfunction "1_P$1") (pintype "passive"))
    )
    (net (code "104") (name "SERVO_3") (class "Default")
      (node (ref "IC3") (pin "13") (pinfunction "GP3_13") (pintype "bidirectional"))
      (node (ref "R20") (pin "P$1") (pinfunction "1_P$1") (pintype "passive"))
      (node (ref "R69") (pin "P$1") (pinfunction "1_P$1") (pintype "passive"))
    )
    (net (code "105") (name "SERVO_4") (class "Default")
      (node (ref "IC3") (pin "14") (pinfunction "GP4_14") (pintype "bidirectional"))
      (node (ref "R25") (pin "P$1") (pinfunction "1_P$1") (pintype "passive"))
      (node (ref "R63") (pin "P$1") (pinfunction "1_P$1") (pintype "passive"))
    )
    (net (code "106") (name "SERVO_5") (class "Default")
      (node (ref "IC3") (pin "15") (pinfunction "GP5_15") (pintype "bidirectional"))
      (node (ref "R30") (pin "P$1") (pinfunction "1_P$1") (pintype "passive"))
      (node (ref "R71") (pin "P$1") (pinfunction "1_P$1") (pintype "passive"))
    )
    (net (code "107") (name "SERVO_6") (class "Default")
      (node (ref "IC3") (pin "16") (pinfunction "GP6_16") (pintype "bidirectional"))
      (node (ref "R35") (pin "P$1") (pinfunction "1_P$1") (pintype "passive"))
      (node (ref "R65") (pin "P$1") (pinfunction "1_P$1") (pintype "passive"))
    )
    (net (code "108") (name "SERVO_7") (class "Default")
      (node (ref "IC3") (pin "17") (pinfunction "GP7_17") (pintype "bidirectional"))
      (node (ref "R40") (pin "P$1") (pinfunction "1_P$1") (pintype "passive"))
      (node (ref "R73") (pin "P$1") (pinfunction "1_P$1") (pintype "passive"))
    )
    (net (code "109") (name "VCC") (class "Default")
      (node (ref "C11") (pin "2") (pinfunction "2_2") (pintype "passive"))
      (node (ref "C12") (pin "1") (pinfunction "1_1") (pintype "passive"))
      (node (ref "C3") (pin "1") (pinfunction "+_1") (pintype "passive"))
      (node (ref "IC3") (pin "18") (pinfunction "VCC_18") (pintype "power_in"))
      (node (ref "JP1") (pin "2") (pinfunction "2_2") (pintype "passive"))
      (node (ref "LED10") (pin "A") (pinfunction "A_A") (pintype "passive"))
      (node (ref "LED3") (pin "A") (pinfunction "A_A") (pintype "passive"))
      (node (ref "LED4") (pin "A") (pinfunction "A_A") (pintype "passive"))
      (node (ref "LED5") (pin "A") (pinfunction "A_A") (pintype "passive"))
      (node (ref "LED6") (pin "A") (pinfunction "A_A") (pintype "passive"))
      (node (ref "LED7") (pin "A") (pinfunction "A_A") (pintype "passive"))
      (node (ref "LED8") (pin "A") (pinfunction "A_A") (pintype "passive"))
      (node (ref "LED9") (pin "A") (pinfunction "A_A") (pintype "passive"))
      (node (ref "Q1") (pin "E") (pinfunction "E_E") (pintype "passive"))
      (node (ref "Q2") (pin "E") (pinfunction "E_E") (pintype "passive"))
      (node (ref "Q3") (pin "E") (pinfunction "E_E") (pintype "passive"))
      (node (ref "Q4") (pin "E") (pinfunction "E_E") (pintype "passive"))
      (node (ref "Q5") (pin "E") (pinfunction "E_E") (pintype "passive"))
      (node (ref "Q6") (pin "E") (pinfunction "E_E") (pintype "passive"))
      (node (ref "Q7") (pin "E") (pinfunction "E_E") (pintype "passive"))
      (node (ref "Q9") (pin "E") (pinfunction "E_E") (pintype "passive"))
      (node (ref "R11") (pin "P$2") (pinfunction "2_P$2") (pintype "passive"))
      (node (ref "R12") (pin "P$2") (pinfunction "2_P$2") (pintype "passive"))
      (node (ref "R45") (pin "P$2") (pinfunction "2_P$2") (pintype "passive"))
      (node (ref "R46") (pin "P$2") (pinfunction "2_P$2") (pintype "passive"))
      (node (ref "R47") (pin "P$2") (pinfunction "2_P$2") (pintype "passive"))
      (node (ref "R50") (pin "P$2") (pinfunction "2_P$2") (pintype "passive"))
      (node (ref "R51") (pin "P$2") (pinfunction "2_P$2") (pintype "passive"))
      (node (ref "R52") (pin "P$2") (pinfunction "2_P$2") (pintype "passive"))
      (node (ref "R54") (pin "P$2") (pinfunction "2_P$2") (pintype "passive"))
      (node (ref "R55") (pin "P$2") (pinfunction "2_P$2") (pintype "passive"))
      (node (ref "R56") (pin "P$2") (pinfunction "2_P$2") (pintype "passive"))
      (node (ref "R57") (pin "P$2") (pinfunction "2_P$2") (pintype "passive"))
      (node (ref "R8") (pin "P$2") (pinfunction "2_P$2") (pintype "passive"))
      (node (ref "R9") (pin "P$2") (pinfunction "2_P$2") (pintype "passive"))
      (node (ref "U1") (pin "28") (pinfunction "VDD_28") (pintype "power_in"))
    )
    (net (code "110") (name "unconnected-(IC3-INT-Pad8)") (class "Default")
      (node (ref "IC3") (pin "8") (pinfunction "INT_8") (pintype "output"))
    )
    (net (code "111") (name "unconnected-(U1-PWM8-Pad15)") (class "Default")
      (node (ref "U1") (pin "15") (pinfunction "PWM8_15") (pintype "output"))
    )
    (net (code "112") (name "unconnected-(U1-PWM9-Pad16)") (class "Default")
      (node (ref "U1") (pin "16") (pinfunction "PWM9_16") (pintype "output"))
    )
    (net (code "113") (name "unconnected-(U1-PWM10-Pad17)") (class "Default")
      (node (ref "U1") (pin "17") (pinfunction "PWM10_17") (pintype "output"))
    )
    (net (code "114") (name "unconnected-(U1-PWM11-Pad18)") (class "Default")
      (node (ref "U1") (pin "18") (pinfunction "PWM11_18") (pintype "output"))
    )
    (net (code "115") (name "unconnected-(U1-PWM12-Pad19)") (class "Default")
      (node (ref "U1") (pin "19") (pinfunction "PWM12_19") (pintype "output"))
    )
    (net (code "116") (name "unconnected-(U1-PWM13-Pad20)") (class "Default")
      (node (ref "U1") (pin "20") (pinfunction "PWM13_20") (pintype "output"))
    )
    (net (code "117") (name "unconnected-(U1-PWM14-Pad21)") (class "Default")
      (node (ref "U1") (pin "21") (pinfunction "PWM14_21") (pintype "output"))
    )
    (net (code "118") (name "unconnected-(U1-PWM15-Pad22)") (class "Default")
      (node (ref "U1") (pin "22") (pinfunction "PWM15_22") (pintype "output"))
    )
  )
)
